# POWER.net
KiCad netlist of a schematic drawn in Altium Designer
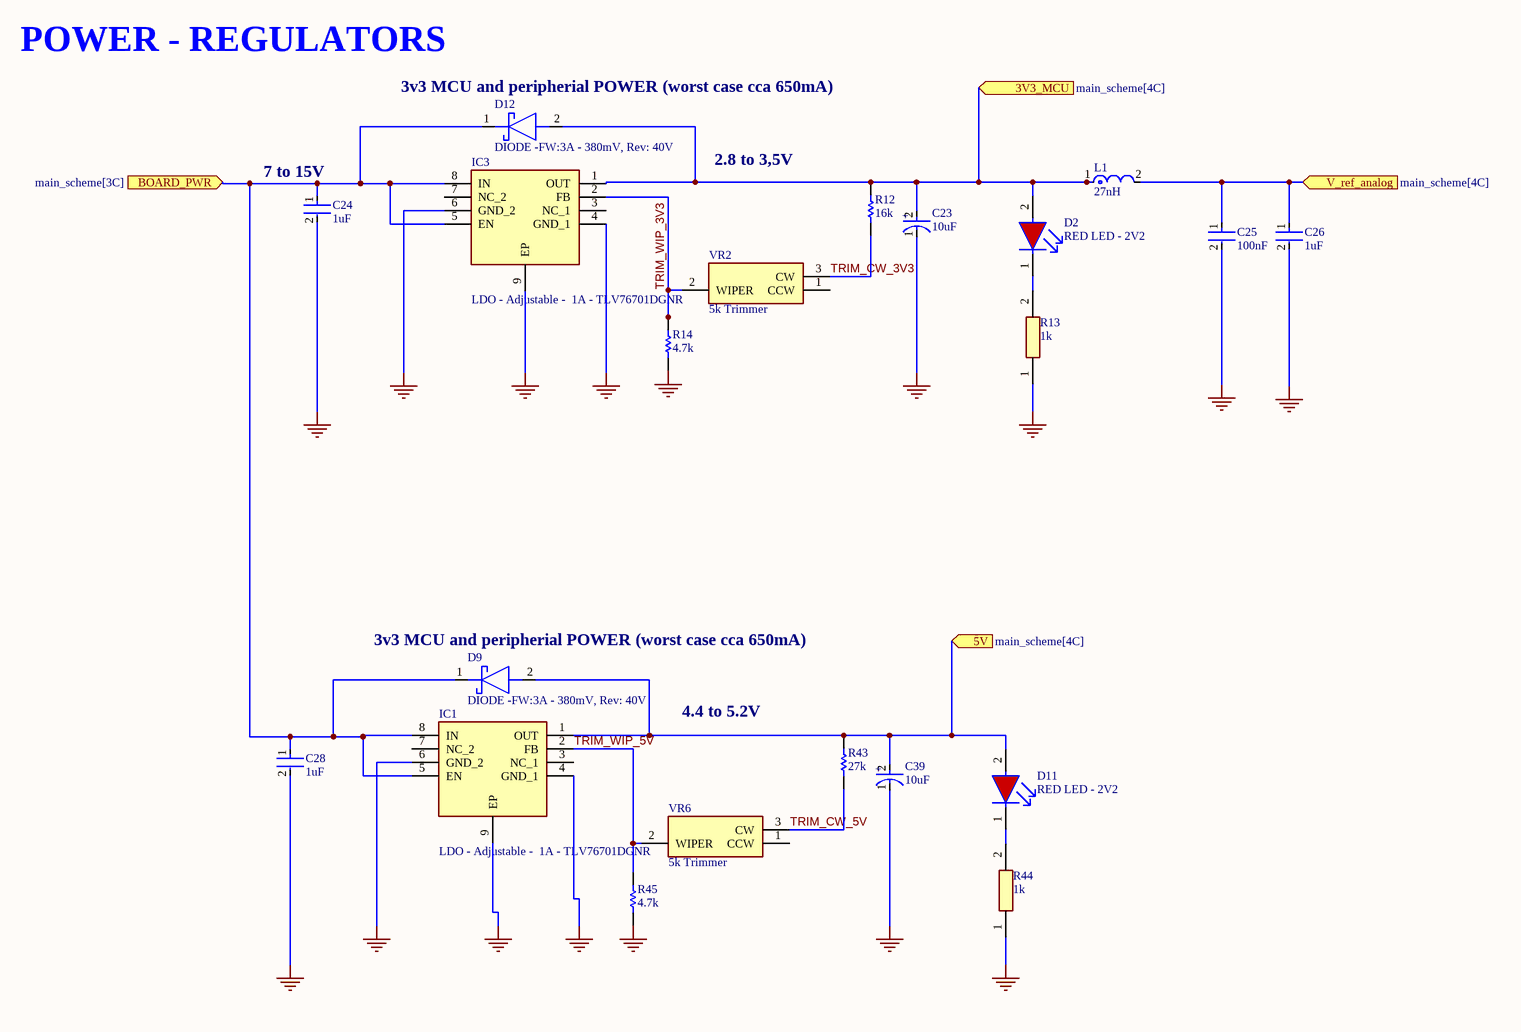
[diagram p0: POWER.SchDoc]

(export (version "E")
  (design (tool "Eeschema 10.0.6"))
  (components
    (comp (ref "C23")
      (value "10uF")
      (footprint "0603_tantal")
      (description "CAP TANT POLY 10UF 10V 0603 20%")
      (fields (field (name "PARTNUMBER") "F381A106MMAAH1"))
      (libsource (lib "Schlib1") (part "CAP 0603 Tantal -10uF"))
    )
    (comp (ref "C24")
      (value "1uF")
      (footprint "0603-CAP")
      (description "General Purpose Ceramic Capacitor, 0603,1uF,25V,10%")
      (fields (field (name "PARTNUMBER") "C1608X7R1E105K080AB"))
      (libsource (lib "Schlib1") (part "CAP-0603-1uF"))
    )
    (comp (ref "C25")
      (value "100nF")
      (footprint "0402 CAP")
      (description "Cap Ceramic 0402,0.1uF, 25V,10%")
      (fields (field (name "PARTNUMBER") "C0402C104K3RACTU"))
      (libsource (lib "Schlib1") (part "CAP 0402 - 100nF"))
    )
    (comp (ref "C26")
      (value "1uF")
      (footprint "0603-CAP")
      (description "General Purpose Ceramic Capacitor, 0603,1uF,25V,10%")
      (fields (field (name "PARTNUMBER") "C1608X7R1E105K080AB"))
      (libsource (lib "Schlib1") (part "CAP-0603-1uF"))
    )
    (comp (ref "C28")
      (value "1uF")
      (footprint "0603-CAP")
      (description "General Purpose Ceramic Capacitor, 0603,1uF,25V,10%")
      (fields (field (name "PARTNUMBER") "C1608X7R1E105K080AB"))
      (libsource (lib "Schlib1") (part "CAP-0603-1uF"))
    )
    (comp (ref "C39")
      (value "10uF")
      (footprint "0603_tantal")
      (description "CAP TANT POLY 10UF 10V 0603 20%")
      (fields (field (name "PARTNUMBER") "F381A106MMAAH1"))
      (libsource (lib "Schlib1") (part "CAP 0603 Tantal -10uF"))
    )
    (comp (ref "D2")
      (value "RED LED - 2V2")
      (footprint "0603_RED_LED")
      (description "LED RED DIFFUSED 0603 SMD")
      (fields (field (name "PARTNUMBER") "SML-D12U1WT86"))
      (libsource (lib "Schlib1") (part "LED - 0603 - RED - 2V2"))
    )
    (comp (ref "D9")
      (value "DIODE -FW:3A - 380mV, Rev: 40V")
      (footprint "PcbLib1:DIONM5127X229N")
      (description "Schottky DIODE -  DO-214AC-2 -FW:3A - 380mV, Rev: 40V")
      (fields (field (name "PARTNUMBER") "SSA34HE3_A/I"))
      (libsource (lib "Schlib1") (part "DIODE -FW{colon}3A - 380mV, Rev{colon} 40V"))
    )
    (comp (ref "D11")
      (value "RED LED - 2V2")
      (footprint "0603_RED_LED")
      (description "LED RED DIFFUSED 0603 SMD")
      (fields (field (name "PARTNUMBER") "SML-D12U1WT86"))
      (libsource (lib "Schlib1") (part "LED - 0603 - RED - 2V2"))
    )
    (comp (ref "D12")
      (value "DIODE -FW:3A - 380mV, Rev: 40V")
      (footprint "PcbLib1:DIONM5127X229N")
      (description "Schottky DIODE -  DO-214AC-2 -FW:3A - 380mV, Rev: 40V")
      (fields (field (name "PARTNUMBER") "SSA34HE3_A/I"))
      (libsource (lib "Schlib1") (part "DIODE -FW{colon}3A - 380mV, Rev{colon} 40V"))
    )
    (comp (ref "IC1")
      (value "LDO - Adjustable -  1A - TLV76701DGNR")
      (footprint "PcbLib1:SOP65P490X110-9N")
      (description "Adjustable  LDO - Input: min 2.5V,max 16V. Output: 0.8V  to 14.6V 1A")
      (fields (field (name "PARTNUMBER") "TLV76701DGNR"))
      (libsource (lib "Schlib1") (part "LDO - Adjustable -  1A - TLV76701DGNR"))
    )
    (comp (ref "IC3")
      (value "LDO - Adjustable -  1A - TLV76701DGNR")
      (footprint "PcbLib1:SOP65P490X110-9N")
      (description "Adjustable  LDO - Input: min 2.5V,max 16V. Output: 0.8V  to 14.6V 1A")
      (fields (field (name "PARTNUMBER") "TLV76701DGNR"))
      (libsource (lib "Schlib1") (part "LDO - Adjustable -  1A - TLV76701DGNR"))
    )
    (comp (ref "L1")
      (value "27nH")
      (footprint "0603-INDUCT")
      (description "Multilayer type RF Inductor 27nH ±5% 0.54Ω 500mA 0603")
      (fields (field (name "PARTNUMBER") "LQG18HN27NJ00D"))
      (libsource (lib "Schlib1") (part "Induct - 0603 -27nH"))
    )
    (comp (ref "R12")
      (value "16k")
      (footprint "RESC1005X40X25NL05T05")
      (description "Resistor - 0402 -  16k - 1% - 100mW")
      (fields (field (name "PARTNUMBER") "ERJ-2RKF1602X"))
      (libsource (lib "Schlib1") (part "Resistor - 0402 - 16k"))
    )
    (comp (ref "R13")
      (value "1k")
      (footprint "PcbLib1:0603- SMD resistor")
      (description "Resistor 0603 1KR 100mW 1%")
      (fields (field (name "PARTNUMBER") "RT0603FRE071KL"))
      (libsource (lib "Schlib1") (part "RESISTOR - 0603 - 1k"))
    )
    (comp (ref "R14")
      (value "4.7k")
      (footprint "RESC1005X40X25NL05T05")
      (description "Resistor - 0402 -  4.7k - 1% - 100mW")
      (fields (field (name "PARTNUMBER") "ERJ-2RKF4701X"))
      (libsource (lib "Schlib1") (part "Resistor - 0402 - 4.7k"))
    )
    (comp (ref "R43")
      (value "27k")
      (footprint "RESC1005X40X25NL05T05")
      (description "Resistor - 0402 - 27k - 1% - 100mW")
      (fields (field (name "PARTNUMBER") "ERJ-H2RD2702X"))
      (libsource (lib "Schlib1") (part "Resistor - 0402 - 27k"))
    )
    (comp (ref "R44")
      (value "1k")
      (footprint "PcbLib1:0603- SMD resistor")
      (description "Resistor 0603 1KR 100mW 1%")
      (fields (field (name "PARTNUMBER") "RT0603FRE071KL"))
      (libsource (lib "Schlib1") (part "RESISTOR - 0603 - 1k"))
    )
    (comp (ref "R45")
      (value "4.7k")
      (footprint "RESC1005X40X25NL05T05")
      (description "Resistor - 0402 -  4.7k - 1% - 100mW")
      (fields (field (name "PARTNUMBER") "ERJ-2RKF4701X"))
      (libsource (lib "Schlib1") (part "Resistor - 0402 - 4.7k"))
    )
    (comp (ref "VR2")
      (value "5k Trimmer")
      (footprint "PcbLib1:TC33X2503E")
      (description "Variable Resistor Trimmer - 5k - 25% -100mW - single turn")
      (fields (field (name "PARTNUMBER") "TC33X-2-502E"))
      (libsource (lib "Schlib1") (part "TRIMMER - 5k -100mW"))
    )
    (comp (ref "VR6")
      (value "5k Trimmer")
      (footprint "PcbLib1:TC33X2503E")
      (description "Variable Resistor Trimmer - 5k - 25% -100mW - single turn")
      (fields (field (name "PARTNUMBER") "TC33X-2-502E"))
      (libsource (lib "Schlib1") (part "TRIMMER - 5k -100mW"))
    )
  )
  (nets
    (net (code "1") (name "/3V3_MCU") (class "Default")
      (node (ref "C23") (pin "2") (pinfunction "A_2") (pintype "passive"))
      (node (ref "D12") (pin "2") (pinfunction "A_2") (pintype "passive"))
      (node (ref "D2") (pin "2") (pinfunction "A_2") (pintype "passive"))
      (node (ref "IC3") (pin "1") (pinfunction "OUT_1") (pintype "passive"))
      (node (ref "L1") (pin "1") (pinfunction "1_1") (pintype "passive"))
      (node (ref "R12") (pin "1") (pinfunction "1_1") (pintype "passive"))
    )
    (net (code "2") (name "/5V") (class "Default")
      (node (ref "C39") (pin "2") (pinfunction "A_2") (pintype "passive"))
      (node (ref "D11") (pin "2") (pinfunction "A_2") (pintype "passive"))
      (node (ref "D9") (pin "2") (pinfunction "A_2") (pintype "passive"))
      (node (ref "IC1") (pin "1") (pinfunction "OUT_1") (pintype "passive"))
      (node (ref "R43") (pin "1") (pinfunction "1_1") (pintype "passive"))
    )
    (net (code "3") (name "/BOARD_PWR") (class "Default")
      (node (ref "C24") (pin "1") (pinfunction "1_1") (pintype "passive"))
      (node (ref "C28") (pin "1") (pinfunction "1_1") (pintype "passive"))
      (node (ref "D12") (pin "1") (pinfunction "K_1") (pintype "passive"))
      (node (ref "D9") (pin "1") (pinfunction "K_1") (pintype "passive"))
      (node (ref "IC1") (pin "5") (pinfunction "EN_5") (pintype "passive"))
      (node (ref "IC1") (pin "8") (pinfunction "IN_8") (pintype "passive"))
      (node (ref "IC3") (pin "5") (pinfunction "EN_5") (pintype "passive"))
      (node (ref "IC3") (pin "8") (pinfunction "IN_8") (pintype "passive"))
    )
    (net (code "4") (name "/TRIM_CW_3V3") (class "Default")
      (node (ref "R12") (pin "2") (pinfunction "2_2") (pintype "passive"))
      (node (ref "VR2") (pin "3") (pinfunction "CW_3") (pintype "passive"))
    )
    (net (code "5") (name "/TRIM_CW_5V") (class "Default")
      (node (ref "R43") (pin "2") (pinfunction "2_2") (pintype "passive"))
      (node (ref "VR6") (pin "3") (pinfunction "CW_3") (pintype "passive"))
    )
    (net (code "6") (name "/TRIM_WIP_3V3") (class "Default")
      (node (ref "IC3") (pin "2") (pinfunction "FB_2") (pintype "passive"))
      (node (ref "R14") (pin "1") (pinfunction "1_1") (pintype "passive"))
      (node (ref "VR2") (pin "2") (pinfunction "WIPER_2") (pintype "passive"))
    )
    (net (code "7") (name "/TRIM_WIP_5V") (class "Default")
      (node (ref "IC1") (pin "2") (pinfunction "FB_2") (pintype "passive"))
      (node (ref "R45") (pin "1") (pinfunction "1_1") (pintype "passive"))
      (node (ref "VR6") (pin "2") (pinfunction "WIPER_2") (pintype "passive"))
    )
    (net (code "8") (name "/V_ref_analog") (class "Default")
      (node (ref "C25") (pin "1") (pinfunction "1_1") (pintype "passive"))
      (node (ref "C26") (pin "1") (pinfunction "1_1") (pintype "passive"))
      (node (ref "L1") (pin "2") (pinfunction "2_2") (pintype "passive"))
    )
    (net (code "9") (name "GND") (class "Default")
      (node (ref "C23") (pin "1") (pinfunction "C_1") (pintype "passive"))
      (node (ref "C24") (pin "2") (pinfunction "2_2") (pintype "passive"))
      (node (ref "C25") (pin "2") (pinfunction "2_2") (pintype "passive"))
      (node (ref "C26") (pin "2") (pinfunction "2_2") (pintype "passive"))
      (node (ref "C28") (pin "2") (pinfunction "2_2") (pintype "passive"))
      (node (ref "C39") (pin "1") (pinfunction "C_1") (pintype "passive"))
      (node (ref "IC1") (pin "4") (pinfunction "GND_1_4") (pintype "passive"))
      (node (ref "IC1") (pin "6") (pinfunction "GND_2_6") (pintype "passive"))
      (node (ref "IC1") (pin "9") (pinfunction "EP_9") (pintype "passive"))
      (node (ref "IC3") (pin "4") (pinfunction "GND_1_4") (pintype "passive"))
      (node (ref "IC3") (pin "6") (pinfunction "GND_2_6") (pintype "passive"))
      (node (ref "IC3") (pin "9") (pinfunction "EP_9") (pintype "passive"))
      (node (ref "R13") (pin "1") (pinfunction "1_1") (pintype "passive"))
      (node (ref "R14") (pin "2") (pinfunction "2_2") (pintype "passive"))
      (node (ref "R44") (pin "1") (pinfunction "1_1") (pintype "passive"))
      (node (ref "R45") (pin "2") (pinfunction "2_2") (pintype "passive"))
    )
    (net (code "10") (name "Net-(D2-C)") (class "Default")
      (node (ref "D2") (pin "1") (pinfunction "C_1") (pintype "passive"))
      (node (ref "R13") (pin "2") (pinfunction "2_2") (pintype "passive"))
    )
    (net (code "11") (name "Net-(D11-C)") (class "Default")
      (node (ref "D11") (pin "1") (pinfunction "C_1") (pintype "passive"))
      (node (ref "R44") (pin "2") (pinfunction "2_2") (pintype "passive"))
    )
    (net (code "12") (name "unconnected-(IC1-NC_1-Pad3)") (class "Default")
      (node (ref "IC1") (pin "3") (pinfunction "NC_1_3") (pintype "passive"))
    )
    (net (code "13") (name "unconnected-(IC1-NC_2-Pad7)") (class "Default")
      (node (ref "IC1") (pin "7") (pinfunction "NC_2_7") (pintype "passive"))
    )
    (net (code "14") (name "unconnected-(IC3-NC_1-Pad3)") (class "Default")
      (node (ref "IC3") (pin "3") (pinfunction "NC_1_3") (pintype "passive"))
    )
    (net (code "15") (name "unconnected-(IC3-NC_2-Pad7)") (class "Default")
      (node (ref "IC3") (pin "7") (pinfunction "NC_2_7") (pintype "passive"))
    )
    (net (code "16") (name "unconnected-(VR2-CCW-Pad1)") (class "Default")
      (node (ref "VR2") (pin "1") (pinfunction "CCW_1") (pintype "passive"))
    )
    (net (code "17") (name "unconnected-(VR6-CCW-Pad1)") (class "Default")
      (node (ref "VR6") (pin "1") (pinfunction "CCW_1") (pintype "passive"))
    )
  )
)
